# Supply_5V_ISOL.net
KiCad netlist of a schematic drawn in Altium Designer
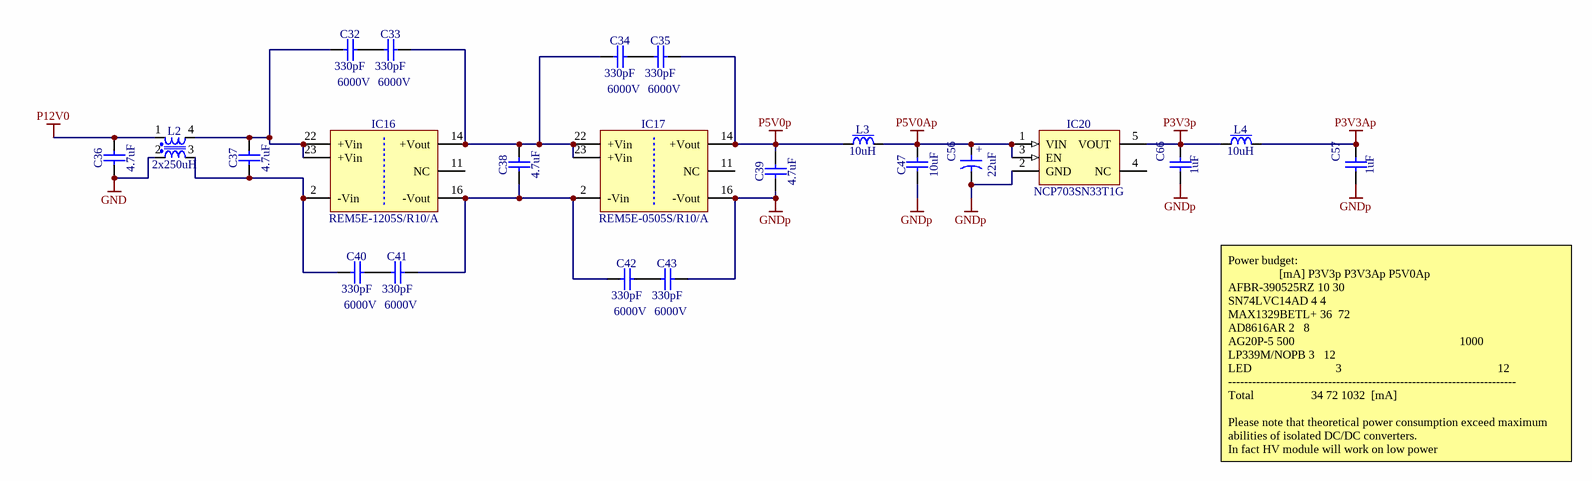
[diagram p0: Supply_5V_ISOL.SchDoc]

(export (version "E")
  (design (tool "Eeschema 10.0.6"))
  (components
    (comp (ref "C32")
      (value "330pF")
      (footprint "CAPC4620X220N")
      (description "Non-polarised capacitor")
      (fields
        (field (name "PART NUMBER") "CC1808_330pF_6000V_10%_X7R_VISHAY_HV")
        (field (name "VOLTAGE") "6000V")
        (field (name "TOLERANCE") "±10%")
        (field (name "AUTHOR") "CERN DEM HF")
      )
      (libsource (lib "Capacitors") (part "Capacitor - non polarized"))
    )
    (comp (ref "C33")
      (value "330pF")
      (footprint "CAPC4620X220N")
      (description "Non-polarised capacitor")
      (fields
        (field (name "PART NUMBER") "CC1808_330pF_6000V_10%_X7R_VISHAY_HV")
        (field (name "VOLTAGE") "6000V")
        (field (name "TOLERANCE") "±10%")
        (field (name "AUTHOR") "CERN DEM HF")
      )
      (libsource (lib "Capacitors") (part "Capacitor - non polarized"))
    )
    (comp (ref "C34")
      (value "330pF")
      (footprint "CAPC4620X220N")
      (description "Non-polarised capacitor")
      (fields
        (field (name "PART NUMBER") "CC1808_330pF_6000V_10%_X7R_VISHAY_HV")
        (field (name "VOLTAGE") "6000V")
        (field (name "TOLERANCE") "±10%")
        (field (name "AUTHOR") "CERN DEM HF")
      )
      (libsource (lib "Capacitors") (part "Capacitor - non polarized"))
    )
    (comp (ref "C35")
      (value "330pF")
      (footprint "CAPC4620X220N")
      (description "Non-polarised capacitor")
      (fields
        (field (name "PART NUMBER") "CC1808_330pF_6000V_10%_X7R_VISHAY_HV")
        (field (name "VOLTAGE") "6000V")
        (field (name "TOLERANCE") "±10%")
        (field (name "AUTHOR") "CERN DEM HF")
      )
      (libsource (lib "Capacitors") (part "Capacitor - non polarized"))
    )
    (comp (ref "C36")
      (value "4.7uF")
      (footprint "CAPC2012X145N")
      (description "Non-polarised capacitor")
      (fields
        (field (name "PART NUMBER") "CC0805_4.7UF_50V_10%_X7R")
        (field (name "VOLTAGE") "50V")
        (field (name "AUTHOR") "CERN DEM JMW")
      )
      (libsource (lib "Capacitors") (part "Capacitor - non polarized"))
    )
    (comp (ref "C37")
      (value "4.7uF")
      (footprint "CAPC2012X145N")
      (description "Non-polarised capacitor")
      (fields
        (field (name "PART NUMBER") "CC0805_4.7UF_50V_10%_X7R")
        (field (name "VOLTAGE") "50V")
        (field (name "AUTHOR") "CERN DEM JMW")
      )
      (libsource (lib "Capacitors") (part "Capacitor - non polarized"))
    )
    (comp (ref "C38")
      (value "4.7uF")
      (footprint "CAPC2012X145N")
      (description "Non-polarised capacitor")
      (fields
        (field (name "PART NUMBER") "CC0805_4.7UF_50V_10%_X7R")
        (field (name "VOLTAGE") "50V")
        (field (name "AUTHOR") "CERN DEM JMW")
      )
      (libsource (lib "Capacitors") (part "Capacitor - non polarized"))
    )
    (comp (ref "C39")
      (value "4.7uF")
      (footprint "CAPC2012X145N")
      (description "Non-polarised capacitor")
      (fields
        (field (name "PART NUMBER") "CC0805_4.7UF_50V_10%_X7R")
        (field (name "VOLTAGE") "50V")
        (field (name "AUTHOR") "CERN DEM JMW")
      )
      (libsource (lib "Capacitors") (part "Capacitor - non polarized"))
    )
    (comp (ref "C40")
      (value "330pF")
      (footprint "CAPC4620X220N")
      (description "Non-polarised capacitor")
      (fields
        (field (name "PART NUMBER") "CC1808_330pF_6000V_10%_X7R_VISHAY_HV")
        (field (name "VOLTAGE") "6000V")
        (field (name "TOLERANCE") "±10%")
        (field (name "AUTHOR") "CERN DEM HF")
      )
      (libsource (lib "Capacitors") (part "Capacitor - non polarized"))
    )
    (comp (ref "C41")
      (value "330pF")
      (footprint "CAPC4620X220N")
      (description "Non-polarised capacitor")
      (fields
        (field (name "PART NUMBER") "CC1808_330pF_6000V_10%_X7R_VISHAY_HV")
        (field (name "VOLTAGE") "6000V")
        (field (name "TOLERANCE") "±10%")
        (field (name "AUTHOR") "CERN DEM HF")
      )
      (libsource (lib "Capacitors") (part "Capacitor - non polarized"))
    )
    (comp (ref "C42")
      (value "330pF")
      (footprint "CAPC4620X220N")
      (description "Non-polarised capacitor")
      (fields
        (field (name "PART NUMBER") "CC1808_330pF_6000V_10%_X7R_VISHAY_HV")
        (field (name "VOLTAGE") "6000V")
        (field (name "TOLERANCE") "±10%")
        (field (name "AUTHOR") "CERN DEM HF")
      )
      (libsource (lib "Capacitors") (part "Capacitor - non polarized"))
    )
    (comp (ref "C43")
      (value "330pF")
      (footprint "CAPC4620X220N")
      (description "Non-polarised capacitor")
      (fields
        (field (name "PART NUMBER") "CC1808_330pF_6000V_10%_X7R_VISHAY_HV")
        (field (name "VOLTAGE") "6000V")
        (field (name "TOLERANCE") "±10%")
        (field (name "AUTHOR") "CERN DEM HF")
      )
      (libsource (lib "Capacitors") (part "Capacitor - non polarized"))
    )
    (comp (ref "C47")
      (value "10uF")
      (footprint "CAPC1608X80N")
      (description "Non-polarised capacitor")
      (fields
        (field (name "PART NUMBER") "CC0603_10UF_16V_20%_X5R")
        (field (name "VOLTAGE") "16V")
        (field (name "AUTHOR") "CERN DEM MR")
      )
      (libsource (lib "Capacitors") (part "Capacitor - non polarized"))
    )
    (comp (ref "C56")
      (value "22uF")
      (footprint "CAPMP3528X210N")
      (description "Polarised capacitor")
      (fields
        (field (name "PART NUMBER") "CTE3528-21_22UF_20V_10%")
        (field (name "VOLTAGE") "20V")
        (field (name "AUTHOR") "CERN DEM JLC")
      )
      (libsource (lib "Capacitors") (part "Capacitor - polarized"))
    )
    (comp (ref "C57")
      (value "1uF")
      (footprint "CAPC1005X55N")
      (description "Non-polarised capacitor")
      (fields
        (field (name "PART NUMBER") "CC0402_1UF_16V_10%_X5R")
        (field (name "VOLTAGE") "16V")
        (field (name "AUTHOR") "CERN DEM JLC")
      )
      (libsource (lib "Capacitors") (part "Capacitor - non polarized"))
    )
    (comp (ref "C66")
      (value "1uF")
      (footprint "CAPC1005X55N")
      (description "Non-polarised capacitor")
      (fields
        (field (name "PART NUMBER") "CC0402_1UF_16V_10%_X5R")
        (field (name "VOLTAGE") "16V")
        (field (name "AUTHOR") "CERN DEM JLC")
      )
      (libsource (lib "Capacitors") (part "Capacitor - non polarized"))
    )
    (comp (ref "IC16")
      (value "REM5E-1205S/R10/A")
      (footprint "DCDC_RECOM_REM5E-XXXXS")
      (description "RECOM, RP Series, Single Output DCDC Converter")
      (fields (field (name "MANUFACTURER") "RECOM") (field (name "AUTHOR") "CERN DEM HF"))
      (libsource (lib "ICs And Semiconductors") (part "DCDC_RECOM_REM5E-XXXXS"))
    )
    (comp (ref "IC17")
      (value "REM5E-0505S/R10/A")
      (footprint "DCDC_RECOM_REM5E-XXXXS")
      (description "RECOM, RP Series, Single Output DCDC Converter")
      (fields (field (name "MANUFACTURER") "RECOM") (field (name "AUTHOR") "CERN DEM HF"))
      (libsource (lib "ICs And Semiconductors") (part "DCDC_RECOM_REM5E-XXXXS"))
    )
    (comp (ref "IC20")
      (value "NCP703SN33T1G")
      (footprint "SOT95P275X110-5N")
      (description "3.3V 300mA, Ultra-Low Quiescent Current, IQ 12uA, Ultra-Low Noise, LDO Voltage Regulator")
      (fields (field (name "MANUFACTURER") "ON SEMICONDUCTOR") (field (name "AUTHOR") "CERN DEM JLC"))
      (libsource (lib "ICs And Semiconductors") (part "NCP703SN"))
    )
    (comp (ref "L2")
      (value "2x250uH")
      (footprint "IND_WURTH_WE-SL2")
      (description "Inductor Common Mode")
      (fields
        (field (name "PART NUMBER") "IND_250UH_50%_WURTH_WE-SL2-744224")
        (field (name "POWER") "1.2A")
        (field (name "AUTHOR") "CERN DEM JLC")
      )
      (libsource (lib "Inductors & Transformers") (part "Inductor Common Mode 1Dot-4 2Dot-3"))
    )
    (comp (ref "L3")
      (value "10uH")
      (footprint "IND_BOURNS_PM43")
      (description "Inductor With Core")
      (fields
        (field (name "PART NUMBER") "IND_10UH_20%_BOURNS_PM43")
        (field (name "POWER") "1.15A")
        (field (name "AUTHOR") "CERN DEM JLC")
      )
      (libsource (lib "Inductors & Transformers") (part "Inductor With Magnetic core"))
    )
    (comp (ref "L4")
      (value "10uH")
      (footprint "IND_BOURNS_PM43")
      (description "Inductor With Core")
      (fields
        (field (name "PART NUMBER") "IND_10UH_20%_BOURNS_PM43")
        (field (name "POWER") "1.15A")
        (field (name "AUTHOR") "CERN DEM JLC")
      )
      (libsource (lib "Inductors & Transformers") (part "Inductor With Magnetic core"))
    )
  )
  (nets
    (net (code "1") (name "GND") (class "Default")
      (node (ref "C36") (pin "1") (pinfunction "1_1") (pintype "passive"))
      (node (ref "L2") (pin "2") (pinfunction "2_2") (pintype "passive"))
    )
    (net (code "2") (name "GNDp") (class "Default")
      (node (ref "C39") (pin "1") (pinfunction "1_1") (pintype "passive"))
      (node (ref "C43") (pin "2") (pinfunction "2_2") (pintype "passive"))
      (node (ref "C47") (pin "1") (pinfunction "1_1") (pintype "passive"))
      (node (ref "C56") (pin "2") (pinfunction "2_2") (pintype "passive"))
      (node (ref "C57") (pin "1") (pinfunction "1_1") (pintype "passive"))
      (node (ref "C66") (pin "1") (pinfunction "1_1") (pintype "passive"))
      (node (ref "IC17") (pin "16") (pinfunction "-Vout_16") (pintype "power_in"))
      (node (ref "IC20") (pin "2") (pinfunction "GND_2") (pintype "power_in"))
    )
    (net (code "3") (name "Net-(C32-Pad1)") (class "Default")
      (node (ref "C32") (pin "1") (pinfunction "1_1") (pintype "passive"))
      (node (ref "C37") (pin "2") (pinfunction "2_2") (pintype "passive"))
      (node (ref "IC16") (pin "22") (pinfunction "+Vin_22") (pintype "power_in"))
      (node (ref "IC16") (pin "23") (pinfunction "+Vin_23") (pintype "power_in"))
      (node (ref "L2") (pin "4") (pinfunction "4_4") (pintype "passive"))
    )
    (net (code "4") (name "Net-(C32-Pad2)") (class "Default")
      (node (ref "C32") (pin "2") (pinfunction "2_2") (pintype "passive"))
      (node (ref "C33") (pin "1") (pinfunction "1_1") (pintype "passive"))
    )
    (net (code "5") (name "Net-(C34-Pad2)") (class "Default")
      (node (ref "C34") (pin "2") (pinfunction "2_2") (pintype "passive"))
      (node (ref "C35") (pin "1") (pinfunction "1_1") (pintype "passive"))
    )
    (net (code "6") (name "Net-(C40-Pad2)") (class "Default")
      (node (ref "C40") (pin "2") (pinfunction "2_2") (pintype "passive"))
      (node (ref "C41") (pin "1") (pinfunction "1_1") (pintype "passive"))
    )
    (net (code "7") (name "Net-(C42-Pad2)") (class "Default")
      (node (ref "C42") (pin "2") (pinfunction "2_2") (pintype "passive"))
      (node (ref "C43") (pin "1") (pinfunction "1_1") (pintype "passive"))
    )
    (net (code "8") (name "Net-(IC16-+Vout)") (class "Default")
      (node (ref "C33") (pin "2") (pinfunction "2_2") (pintype "passive"))
      (node (ref "C34") (pin "1") (pinfunction "1_1") (pintype "passive"))
      (node (ref "C38") (pin "2") (pinfunction "2_2") (pintype "passive"))
      (node (ref "IC16") (pin "14") (pinfunction "+Vout_14") (pintype "power_in"))
      (node (ref "IC17") (pin "22") (pinfunction "+Vin_22") (pintype "power_in"))
      (node (ref "IC17") (pin "23") (pinfunction "+Vin_23") (pintype "power_in"))
    )
    (net (code "9") (name "Net-(IC16--Vin)") (class "Default")
      (node (ref "C37") (pin "1") (pinfunction "1_1") (pintype "passive"))
      (node (ref "C40") (pin "1") (pinfunction "1_1") (pintype "passive"))
      (node (ref "IC16") (pin "2") (pinfunction "-Vin_2") (pintype "power_in"))
      (node (ref "L2") (pin "3") (pinfunction "3_3") (pintype "passive"))
    )
    (net (code "10") (name "Net-(IC16--Vout)") (class "Default")
      (node (ref "C38") (pin "1") (pinfunction "1_1") (pintype "passive"))
      (node (ref "C41") (pin "2") (pinfunction "2_2") (pintype "passive"))
      (node (ref "C42") (pin "1") (pinfunction "1_1") (pintype "passive"))
      (node (ref "IC16") (pin "16") (pinfunction "-Vout_16") (pintype "power_in"))
      (node (ref "IC17") (pin "2") (pinfunction "-Vin_2") (pintype "power_in"))
    )
    (net (code "11") (name "P3V3Ap") (class "Default")
      (node (ref "C57") (pin "2") (pinfunction "2_2") (pintype "passive"))
      (node (ref "L4") (pin "2") (pinfunction "2_2") (pintype "passive"))
    )
    (net (code "12") (name "P3V3p") (class "Default")
      (node (ref "C66") (pin "2") (pinfunction "2_2") (pintype "passive"))
      (node (ref "IC20") (pin "5") (pinfunction "VOUT_5") (pintype "power_in"))
      (node (ref "L4") (pin "1") (pinfunction "1_1") (pintype "passive"))
    )
    (net (code "13") (name "P5V0Ap") (class "Default")
      (node (ref "C47") (pin "2") (pinfunction "2_2") (pintype "passive"))
      (node (ref "C56") (pin "1") (pinfunction "1_1") (pintype "passive"))
      (node (ref "IC20") (pin "1") (pinfunction "VIN_1") (pintype "input"))
      (node (ref "IC20") (pin "3") (pinfunction "EN_3") (pintype "input"))
      (node (ref "L3") (pin "2") (pinfunction "2_2") (pintype "passive"))
    )
    (net (code "14") (name "P5V0p") (class "Default")
      (node (ref "C35") (pin "2") (pinfunction "2_2") (pintype "passive"))
      (node (ref "C39") (pin "2") (pinfunction "2_2") (pintype "passive"))
      (node (ref "IC17") (pin "14") (pinfunction "+Vout_14") (pintype "power_in"))
      (node (ref "L3") (pin "1") (pinfunction "1_1") (pintype "passive"))
    )
    (net (code "15") (name "P12V0") (class "Default")
      (node (ref "C36") (pin "2") (pinfunction "2_2") (pintype "passive"))
      (node (ref "L2") (pin "1") (pinfunction "1_1") (pintype "passive"))
    )
    (net (code "16") (name "unconnected-(IC16-NC-Pad11)") (class "Default")
      (node (ref "IC16") (pin "11") (pinfunction "NC_11") (pintype "power_in"))
    )
    (net (code "17") (name "unconnected-(IC17-NC-Pad11)") (class "Default")
      (node (ref "IC17") (pin "11") (pinfunction "NC_11") (pintype "power_in"))
    )
    (net (code "18") (name "unconnected-(IC20-NC-Pad4)") (class "Default")
      (node (ref "IC20") (pin "4") (pinfunction "NC_4") (pintype "passive"))
    )
  )
)
